# SparkFun_GPS_NEO_M9N_ANT_PROTO2.net
KiCad netlist of a schematic drawn in EAGLE
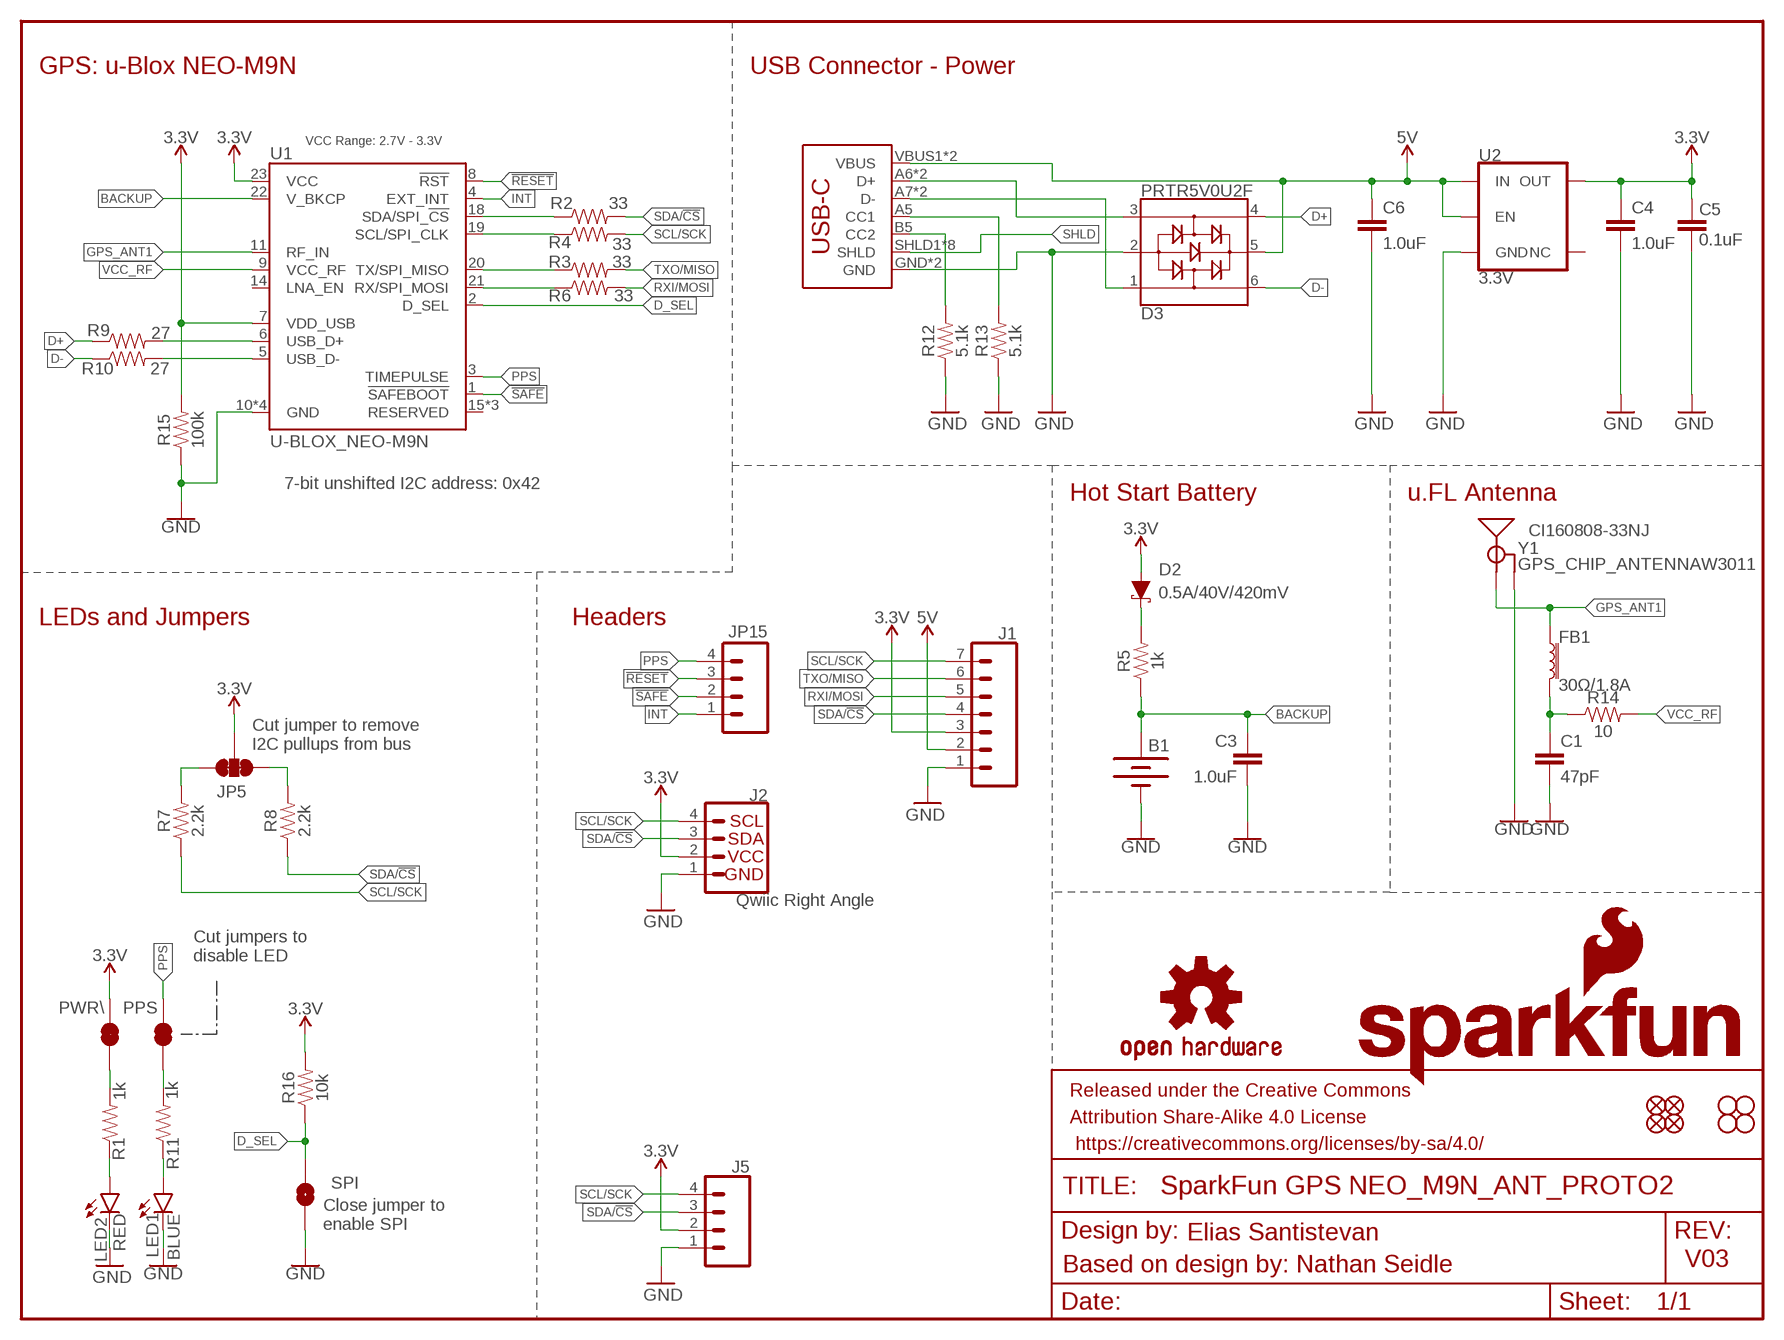
[diagram p0: schematic, sheet 1]

(export (version "E")
  (design (tool "Eeschema 10.0.6"))
  (components
    (comp (ref "B1")
      (value "6.8MM_COIN_CELL")
      (footprint "eagle-import:ML414H_IV01E")
      (libsource (lib "eagle-import") (part "ML414H_IV01E_BATTERY"))
    )
    (comp (ref "C1")
      (value "47pF")
      (footprint "eagle-import:0603")
      (libsource (lib "eagle-import") (part "47PF-0603-50V-5%"))
    )
    (comp (ref "C3")
      (value "1.0uF")
      (footprint "eagle-import:0603")
      (libsource (lib "eagle-import") (part "1.0UF-0603-16V-10%"))
    )
    (comp (ref "C4")
      (value "1.0uF")
      (footprint "eagle-import:0603")
      (libsource (lib "eagle-import") (part "1.0UF-0603-16V-10%"))
    )
    (comp (ref "C5")
      (value "0.1uF")
      (footprint "eagle-import:0603")
      (libsource (lib "eagle-import") (part "0.1UF-0603-25V-(+80/-20%)"))
    )
    (comp (ref "C6")
      (value "1.0uF")
      (footprint "eagle-import:0603")
      (libsource (lib "eagle-import") (part "1.0UF-0603-16V-10%"))
    )
    (comp (ref "D2")
      (value "0.5A/40V/420mV")
      (footprint "eagle-import:SOD-323")
      (libsource (lib "eagle-import") (part "DIODE-SCHOTTKY-PMEG4005EJ"))
    )
    (comp (ref "D3")
      (value "PRTR5V0U2F")
      (footprint "eagle-import:SOT886")
      (libsource (lib "eagle-import") (part "PRTR5V0U2F"))
    )
    (comp (ref "FB1")
      (value "30Ω/1.8A")
      (footprint "eagle-import:0603")
      (libsource (lib "eagle-import") (part "FERRITE_BEAD-0603"))
    )
    (comp (ref "FRAME1")
      (value "FRAME-LETTER")
      (footprint "eagle-import:CREATIVE_COMMONS")
      (libsource (lib "eagle-import") (part "FRAME-LETTER"))
    )
    (comp (ref "J1")
      (value "CONN_07NO_SILK")
      (footprint "eagle-import:1X07_NO_SILK")
      (libsource (lib "eagle-import") (part "CONN_07NO_SILK"))
    )
    (comp (ref "J2")
      (value "Qwiic Right Angle")
      (footprint "eagle-import:JST04_1MM_RA")
      (libsource (lib "eagle-import") (part "I2C_STANDARDQWIIC"))
    )
    (comp (ref "J3")
      (value "USB_C2-LAYER")
      (footprint "eagle-import:USB-C-16P")
      (libsource (lib "eagle-import") (part "USB_C2-LAYER"))
    )
    (comp (ref "J5")
      (value "CONN_041X04_NO_SILK")
      (footprint "eagle-import:1X04_NO_SILK")
      (libsource (lib "eagle-import") (part "CONN_041X04_NO_SILK"))
    )
    (comp (ref "JP5")
      (value "JUMPER-SMT_3_2-NC_TRACE_SILK")
      (footprint "eagle-import:SMT-JUMPER_3_2-NC_TRACE_SILK")
      (libsource (lib "eagle-import") (part "JUMPER-SMT_3_2-NC_TRACE_SILK"))
    )
    (comp (ref "JP15")
      (value "CONN_041X04_NO_SILK")
      (footprint "eagle-import:1X04_NO_SILK")
      (libsource (lib "eagle-import") (part "CONN_041X04_NO_SILK"))
    )
    (comp (ref "JP21")
      (value "FIDUCIALUFIDUCIAL")
      (footprint "eagle-import:MICRO-FIDUCIAL")
      (libsource (lib "eagle-import") (part "FIDUCIALUFIDUCIAL"))
    )
    (comp (ref "JP31")
      (value "STAND-OFF")
      (footprint "eagle-import:STAND-OFF")
      (libsource (lib "eagle-import") (part "STAND-OFF"))
    )
    (comp (ref "JP41")
      (value "STAND-OFF")
      (footprint "eagle-import:STAND-OFF")
      (libsource (lib "eagle-import") (part "STAND-OFF"))
    )
    (comp (ref "JP61")
      (value "FIDUCIALUFIDUCIAL")
      (footprint "eagle-import:MICRO-FIDUCIAL")
      (libsource (lib "eagle-import") (part "FIDUCIALUFIDUCIAL"))
    )
    (comp (ref "JP71")
      (value "FIDUCIALUFIDUCIAL")
      (footprint "eagle-import:MICRO-FIDUCIAL")
      (libsource (lib "eagle-import") (part "FIDUCIALUFIDUCIAL"))
    )
    (comp (ref "JP81")
      (value "FIDUCIALUFIDUCIAL")
      (footprint "eagle-import:MICRO-FIDUCIAL")
      (libsource (lib "eagle-import") (part "FIDUCIALUFIDUCIAL"))
    )
    (comp (ref "JP91")
      (value "STAND-OFF")
      (footprint "eagle-import:STAND-OFF")
      (libsource (lib "eagle-import") (part "STAND-OFF"))
    )
    (comp (ref "JP101")
      (value "STAND-OFF")
      (footprint "eagle-import:STAND-OFF")
      (libsource (lib "eagle-import") (part "STAND-OFF"))
    )
    (comp (ref "LED1")
      (value "BLUE")
      (footprint "eagle-import:LED-0603")
      (libsource (lib "eagle-import") (part "LED-BLUE0603"))
    )
    (comp (ref "LED2")
      (value "RED")
      (footprint "eagle-import:LED-0603")
      (libsource (lib "eagle-import") (part "LED-RED0603"))
    )
    (comp (ref "LOGO1")
      (value "OSHW-LOGOMINI")
      (footprint "eagle-import:OSHW-LOGO-MINI")
      (libsource (lib "eagle-import") (part "OSHW-LOGOMINI"))
    )
    (comp (ref "LOGO2")
      (value "SFE_LOGO_NAME_FLAME.1_INCH")
      (footprint "eagle-import:SFE_LOGO_NAME_FLAME_.1")
      (libsource (lib "eagle-import") (part "SFE_LOGO_NAME_FLAME.1_INCH"))
    )
    (comp (ref "PPS")
      (value "JUMPER-SMT_2_NC_TRACE_SILK")
      (footprint "eagle-import:SMT-JUMPER_2_NC_TRACE_SILK")
      (libsource (lib "eagle-import") (part "JUMPER-SMT_2_NC_TRACE_SILK"))
    )
    (comp (ref "PWR\\")
      (value "JUMPER-SMT_2_NC_TRACE_SILK")
      (footprint "eagle-import:SMT-JUMPER_2_NC_TRACE_SILK")
      (libsource (lib "eagle-import") (part "JUMPER-SMT_2_NC_TRACE_SILK"))
    )
    (comp (ref "R1")
      (value "1k")
      (footprint "eagle-import:0603")
      (libsource (lib "eagle-import") (part "1KOHM-0603-1/10W-1%"))
    )
    (comp (ref "R2")
      (value "33")
      (footprint "eagle-import:0603")
      (libsource (lib "eagle-import") (part "33OHM-0603-1/10W-1%"))
    )
    (comp (ref "R3")
      (value "33")
      (footprint "eagle-import:0603")
      (libsource (lib "eagle-import") (part "33OHM-0603-1/10W-1%"))
    )
    (comp (ref "R4")
      (value "33")
      (footprint "eagle-import:0603")
      (libsource (lib "eagle-import") (part "33OHM-0603-1/10W-1%"))
    )
    (comp (ref "R5")
      (value "1k")
      (footprint "eagle-import:0603")
      (libsource (lib "eagle-import") (part "1KOHM-0603-1/10W-1%"))
    )
    (comp (ref "R6")
      (value "33")
      (footprint "eagle-import:0603")
      (libsource (lib "eagle-import") (part "33OHM-0603-1/10W-1%"))
    )
    (comp (ref "R7")
      (value "2.2k")
      (footprint "eagle-import:0603")
      (libsource (lib "eagle-import") (part "2.2KOHM-0603-1/10W-1%"))
    )
    (comp (ref "R8")
      (value "2.2k")
      (footprint "eagle-import:0603")
      (libsource (lib "eagle-import") (part "2.2KOHM-0603-1/10W-1%"))
    )
    (comp (ref "R9")
      (value "27")
      (footprint "eagle-import:0603")
      (libsource (lib "eagle-import") (part "27OHM-0603-1/10W-1%"))
    )
    (comp (ref "R10")
      (value "27")
      (footprint "eagle-import:0603")
      (libsource (lib "eagle-import") (part "27OHM-0603-1/10W-1%"))
    )
    (comp (ref "R11")
      (value "1k")
      (footprint "eagle-import:0603")
      (libsource (lib "eagle-import") (part "1KOHM-0603-1/10W-1%"))
    )
    (comp (ref "R12")
      (value "5.1k")
      (footprint "eagle-import:0603")
      (libsource (lib "eagle-import") (part "5.1KOHM5.1KOHM-0603-1/10W-1%"))
    )
    (comp (ref "R13")
      (value "5.1k")
      (footprint "eagle-import:0603")
      (libsource (lib "eagle-import") (part "5.1KOHM5.1KOHM-0603-1/10W-1%"))
    )
    (comp (ref "R14")
      (value "10")
      (footprint "eagle-import:0603")
      (libsource (lib "eagle-import") (part "10OHM-0603-1/10W-1%"))
    )
    (comp (ref "R15")
      (value "100k")
      (footprint "eagle-import:0603")
      (libsource (lib "eagle-import") (part "100KOHM-0603-1/10W-1%"))
    )
    (comp (ref "R16")
      (value "10k")
      (footprint "eagle-import:0402")
      (libsource (lib "eagle-import") (part "10KOHM-0402-1/16W-1%"))
    )
    (comp (ref "SPI")
      (value "JUMPER-SMT_2_NO_SILK")
      (footprint "eagle-import:SMT-JUMPER_2_NO_SILK")
      (libsource (lib "eagle-import") (part "JUMPER-SMT_2_NO_SILK"))
    )
    (comp (ref "U1")
      (value "U-BLOX_NEO-M9N")
      (footprint "eagle-import:NEO-M9N")
      (libsource (lib "eagle-import") (part "U-BLOX_NEO-M9N"))
    )
    (comp (ref "U2")
      (value "3.3V")
      (footprint "eagle-import:SOT23-5")
      (libsource (lib "eagle-import") (part "V_REG_AP2112K-3.3V"))
    )
    (comp (ref "Y1")
      (value "GPS_CHIP_ANTENNAW3011")
      (footprint "eagle-import:W3011")
      (libsource (lib "eagle-import") (part "GPS_CHIP_ANTENNAW3011"))
    )
  )
  (nets
    (net (code "1") (name "/SDA{slash}~{CS}") (class "Default")
      (node (ref "J1") (pin "4") (pinfunction "4_4") (pintype "passive"))
      (node (ref "J2") (pin "3") (pinfunction "3_3") (pintype "passive"))
      (node (ref "J5") (pin "3") (pinfunction "3_3") (pintype "passive"))
      (node (ref "R2") (pin "2") (pinfunction "2_2") (pintype "passive"))
      (node (ref "R8") (pin "1") (pinfunction "1_1") (pintype "passive"))
    )
    (net (code "2") (name "/~{RESET}") (class "Default")
      (node (ref "JP15") (pin "3") (pinfunction "3_3") (pintype "passive"))
      (node (ref "U1") (pin "8") (pinfunction "~{RST}_8") (pintype "bidirectional"))
    )
    (net (code "3") (name "/~{SAFE}") (class "Default")
      (node (ref "JP15") (pin "2") (pinfunction "2_2") (pintype "passive"))
      (node (ref "U1") (pin "1") (pinfunction "~{SAFEBOOT}_1") (pintype "bidirectional"))
    )
    (net (code "4") (name "3.3V") (class "Default")
      (node (ref "C4") (pin "1") (pinfunction "1_1") (pintype "passive"))
      (node (ref "C5") (pin "2") (pinfunction "2_2") (pintype "passive"))
      (node (ref "D2") (pin "A") (pinfunction "A_A") (pintype "passive"))
      (node (ref "J1") (pin "3") (pinfunction "3_3") (pintype "passive"))
      (node (ref "J2") (pin "2") (pinfunction "2_2") (pintype "power_in"))
      (node (ref "J5") (pin "2") (pinfunction "2_2") (pintype "passive"))
      (node (ref "JP5") (pin "2") (pinfunction "2_2") (pintype "passive"))
      (node (ref "PWR\\") (pin "2") (pinfunction "2_2") (pintype "passive"))
      (node (ref "R15") (pin "2") (pinfunction "2_2") (pintype "passive"))
      (node (ref "R16") (pin "2") (pinfunction "2_2") (pintype "passive"))
      (node (ref "U1") (pin "23") (pinfunction "VCC_23") (pintype "bidirectional"))
      (node (ref "U1") (pin "7") (pinfunction "VDD_USB_7") (pintype "bidirectional"))
      (node (ref "U2") (pin "5") (pinfunction "OUT_5") (pintype "passive"))
    )
    (net (code "5") (name "5V") (class "Default")
      (node (ref "C6") (pin "1") (pinfunction "1_1") (pintype "passive"))
      (node (ref "D3") (pin "5") (pinfunction "5_5") (pintype "bidirectional"))
      (node (ref "J1") (pin "2") (pinfunction "2_2") (pintype "passive"))
      (node (ref "J3") (pin "VBUS1") (pinfunction "VBUS_VBUS1") (pintype "bidirectional"))
      (node (ref "J3") (pin "VBUS2") (pinfunction "VBUS_VBUS2") (pintype "bidirectional"))
      (node (ref "U2") (pin "1") (pinfunction "IN_1") (pintype "input"))
      (node (ref "U2") (pin "3") (pinfunction "EN_3") (pintype "input"))
    )
    (net (code "6") (name "BACKUP") (class "Default")
      (node (ref "B1") (pin "+") (pinfunction "+_+") (pintype "power_in"))
      (node (ref "C3") (pin "1") (pinfunction "1_1") (pintype "passive"))
      (node (ref "R5") (pin "1") (pinfunction "1_1") (pintype "passive"))
      (node (ref "U1") (pin "22") (pinfunction "V_BKCP_22") (pintype "bidirectional"))
    )
    (net (code "7") (name "D+") (class "Default")
      (node (ref "D3") (pin "4") (pinfunction "4_4") (pintype "bidirectional"))
      (node (ref "R9") (pin "1") (pinfunction "1_1") (pintype "passive"))
    )
    (net (code "8") (name "D-") (class "Default")
      (node (ref "D3") (pin "6") (pinfunction "6_6") (pintype "bidirectional"))
      (node (ref "R10") (pin "1") (pinfunction "1_1") (pintype "passive"))
    )
    (net (code "9") (name "D_SEL") (class "Default")
      (node (ref "R16") (pin "1") (pinfunction "1_1") (pintype "passive"))
      (node (ref "SPI") (pin "2") (pinfunction "2_2") (pintype "passive"))
      (node (ref "U1") (pin "2") (pinfunction "D_SEL_2") (pintype "bidirectional"))
    )
    (net (code "10") (name "GND") (class "Default")
      (node (ref "B1") (pin "-") (pinfunction "-_-") (pintype "power_in"))
      (node (ref "C1") (pin "2") (pinfunction "2_2") (pintype "passive"))
      (node (ref "C3") (pin "2") (pinfunction "2_2") (pintype "passive"))
      (node (ref "C4") (pin "2") (pinfunction "2_2") (pintype "passive"))
      (node (ref "C5") (pin "1") (pinfunction "1_1") (pintype "passive"))
      (node (ref "C6") (pin "2") (pinfunction "2_2") (pintype "passive"))
      (node (ref "D3") (pin "2") (pinfunction "2_2") (pintype "bidirectional"))
      (node (ref "J1") (pin "1") (pinfunction "1_1") (pintype "passive"))
      (node (ref "J2") (pin "1") (pinfunction "1_1") (pintype "power_in"))
      (node (ref "J3") (pin "GND") (pinfunction "GND_GND") (pintype "bidirectional"))
      (node (ref "J3") (pin "GND2") (pinfunction "GND_GND2") (pintype "bidirectional"))
      (node (ref "J5") (pin "1") (pinfunction "1_1") (pintype "passive"))
      (node (ref "LED1") (pin "C") (pinfunction "C_C") (pintype "passive"))
      (node (ref "LED2") (pin "C") (pinfunction "C_C") (pintype "passive"))
      (node (ref "R12") (pin "1") (pinfunction "1_1") (pintype "passive"))
      (node (ref "R13") (pin "1") (pinfunction "1_1") (pintype "passive"))
      (node (ref "R15") (pin "1") (pinfunction "1_1") (pintype "passive"))
      (node (ref "SPI") (pin "1") (pinfunction "1_1") (pintype "passive"))
      (node (ref "U1") (pin "10") (pinfunction "GND_10") (pintype "bidirectional"))
      (node (ref "U1") (pin "12") (pinfunction "GND_12") (pintype "bidirectional"))
      (node (ref "U1") (pin "13") (pinfunction "GND_13") (pintype "bidirectional"))
      (node (ref "U1") (pin "24") (pinfunction "GND_24") (pintype "bidirectional"))
      (node (ref "U2") (pin "2") (pinfunction "GND_2") (pintype "input"))
      (node (ref "Y1") (pin "2") (pinfunction "GND_2") (pintype "bidirectional"))
      (node (ref "Y1") (pin "3") (pinfunction "GND_3") (pintype "bidirectional"))
    )
    (net (code "11") (name "GPS_ANT1") (class "Default")
      (node (ref "FB1") (pin "1") (pinfunction "1_1") (pintype "passive"))
      (node (ref "U1") (pin "11") (pinfunction "RF_IN_11") (pintype "bidirectional"))
      (node (ref "Y1") (pin "1") (pinfunction "SIGNAL_1") (pintype "bidirectional"))
    )
    (net (code "12") (name "INT") (class "Default")
      (node (ref "JP15") (pin "1") (pinfunction "1_1") (pintype "passive"))
      (node (ref "U1") (pin "4") (pinfunction "EXT_INT_4") (pintype "bidirectional"))
    )
    (net (code "13") (name "Net-(C1-Pad1)") (class "Default")
      (node (ref "C1") (pin "1") (pinfunction "1_1") (pintype "passive"))
      (node (ref "FB1") (pin "2") (pinfunction "2_2") (pintype "passive"))
      (node (ref "R14") (pin "1") (pinfunction "1_1") (pintype "passive"))
    )
    (net (code "14") (name "Net-(D2-PadC)") (class "Default")
      (node (ref "D2") (pin "C") (pinfunction "C_C") (pintype "passive"))
      (node (ref "R5") (pin "2") (pinfunction "2_2") (pintype "passive"))
    )
    (net (code "15") (name "Net-(D3-Pad1)") (class "Default")
      (node (ref "D3") (pin "1") (pinfunction "1_1") (pintype "bidirectional"))
      (node (ref "J3") (pin "A7") (pinfunction "D-_A7") (pintype "bidirectional"))
      (node (ref "J3") (pin "B7") (pinfunction "D-_B7") (pintype "bidirectional"))
    )
    (net (code "16") (name "Net-(D3-Pad3)") (class "Default")
      (node (ref "D3") (pin "3") (pinfunction "3_3") (pintype "bidirectional"))
      (node (ref "J3") (pin "A6") (pinfunction "D+_A6") (pintype "bidirectional"))
      (node (ref "J3") (pin "B6") (pinfunction "D+_B6") (pintype "bidirectional"))
    )
    (net (code "17") (name "Net-(J3-CC1)") (class "Default")
      (node (ref "J3") (pin "A5") (pinfunction "CC1_A5") (pintype "bidirectional"))
      (node (ref "R13") (pin "2") (pinfunction "2_2") (pintype "passive"))
    )
    (net (code "18") (name "Net-(J3-CC2)") (class "Default")
      (node (ref "J3") (pin "B5") (pinfunction "CC2_B5") (pintype "bidirectional"))
      (node (ref "R12") (pin "2") (pinfunction "2_2") (pintype "passive"))
    )
    (net (code "19") (name "Net-(JP5-Pad1)") (class "Default")
      (node (ref "JP5") (pin "1") (pinfunction "1_1") (pintype "passive"))
      (node (ref "R8") (pin "2") (pinfunction "2_2") (pintype "passive"))
    )
    (net (code "20") (name "Net-(JP5-Pad3)") (class "Default")
      (node (ref "JP5") (pin "3") (pinfunction "3_3") (pintype "passive"))
      (node (ref "R7") (pin "2") (pinfunction "2_2") (pintype "passive"))
    )
    (net (code "21") (name "Net-(LED1-PadA)") (class "Default")
      (node (ref "LED1") (pin "A") (pinfunction "A_A") (pintype "passive"))
      (node (ref "R11") (pin "1") (pinfunction "1_1") (pintype "passive"))
    )
    (net (code "22") (name "Net-(LED2-PadA)") (class "Default")
      (node (ref "LED2") (pin "A") (pinfunction "A_A") (pintype "passive"))
      (node (ref "R1") (pin "1") (pinfunction "1_1") (pintype "passive"))
    )
    (net (code "23") (name "Net-(PPS-Pad1)") (class "Default")
      (node (ref "PPS") (pin "1") (pinfunction "1_1") (pintype "passive"))
      (node (ref "R11") (pin "2") (pinfunction "2_2") (pintype "passive"))
    )
    (net (code "24") (name "Net-(PWR\\-Pad1)") (class "Default")
      (node (ref "PWR\\") (pin "1") (pinfunction "1_1") (pintype "passive"))
      (node (ref "R1") (pin "2") (pinfunction "2_2") (pintype "passive"))
    )
    (net (code "25") (name "Net-(U1-RX{slash}SPI_MOSI)") (class "Default")
      (node (ref "R6") (pin "1") (pinfunction "1_1") (pintype "passive"))
      (node (ref "U1") (pin "21") (pinfunction "RX/SPI_MOSI_21") (pintype "bidirectional"))
    )
    (net (code "26") (name "Net-(U1-SCL{slash}SPI_CLK)") (class "Default")
      (node (ref "R4") (pin "1") (pinfunction "1_1") (pintype "passive"))
      (node (ref "U1") (pin "19") (pinfunction "SCL/SPI_CLK_19") (pintype "bidirectional"))
    )
    (net (code "27") (name "Net-(U1-SDA{slash}SPI_~{CS})") (class "Default")
      (node (ref "R2") (pin "1") (pinfunction "1_1") (pintype "passive"))
      (node (ref "U1") (pin "18") (pinfunction "SDA/SPI_~{CS}_18") (pintype "bidirectional"))
    )
    (net (code "28") (name "Net-(U1-TX{slash}SPI_MISO)") (class "Default")
      (node (ref "R3") (pin "1") (pinfunction "1_1") (pintype "passive"))
      (node (ref "U1") (pin "20") (pinfunction "TX/SPI_MISO_20") (pintype "bidirectional"))
    )
    (net (code "29") (name "Net-(U1-USB_D+)") (class "Default")
      (node (ref "R9") (pin "2") (pinfunction "2_2") (pintype "passive"))
      (node (ref "U1") (pin "6") (pinfunction "USB_D+_6") (pintype "bidirectional"))
    )
    (net (code "30") (name "Net-(U1-USB_D-)") (class "Default")
      (node (ref "R10") (pin "2") (pinfunction "2_2") (pintype "passive"))
      (node (ref "U1") (pin "5") (pinfunction "USB_D-_5") (pintype "bidirectional"))
    )
    (net (code "31") (name "PPS") (class "Default")
      (node (ref "JP15") (pin "4") (pinfunction "4_4") (pintype "passive"))
      (node (ref "PPS") (pin "2") (pinfunction "2_2") (pintype "passive"))
      (node (ref "U1") (pin "3") (pinfunction "TIMEPULSE_3") (pintype "bidirectional"))
    )
    (net (code "32") (name "RXI{slash}MOSI") (class "Default")
      (node (ref "J1") (pin "5") (pinfunction "5_5") (pintype "passive"))
      (node (ref "R6") (pin "2") (pinfunction "2_2") (pintype "passive"))
    )
    (net (code "33") (name "SCL{slash}SCK") (class "Default")
      (node (ref "J1") (pin "7") (pinfunction "7_7") (pintype "passive"))
      (node (ref "J2") (pin "4") (pinfunction "4_4") (pintype "passive"))
      (node (ref "J5") (pin "4") (pinfunction "4_4") (pintype "passive"))
      (node (ref "R4") (pin "2") (pinfunction "2_2") (pintype "passive"))
      (node (ref "R7") (pin "1") (pinfunction "1_1") (pintype "passive"))
    )
    (net (code "34") (name "SHLD") (class "Default")
      (node (ref "J3") (pin "SHLD1") (pinfunction "SHLD_SHLD1") (pintype "bidirectional"))
      (node (ref "J3") (pin "SHLD2") (pinfunction "SHLD_SHLD2") (pintype "bidirectional"))
      (node (ref "J3") (pin "SHLD3") (pinfunction "SHLD_SHLD3") (pintype "bidirectional"))
      (node (ref "J3") (pin "SHLD4") (pinfunction "SHLD_SHLD4") (pintype "bidirectional"))
      (node (ref "J3") (pin "SHLD5") (pinfunction "SHLD_SHLD5") (pintype "bidirectional"))
      (node (ref "J3") (pin "SHLD6") (pinfunction "SHLD_SHLD6") (pintype "bidirectional"))
      (node (ref "J3") (pin "SHLD7") (pinfunction "SHLD_SHLD7") (pintype "bidirectional"))
      (node (ref "J3") (pin "SHLD8") (pinfunction "SHLD_SHLD8") (pintype "bidirectional"))
    )
    (net (code "35") (name "TXO{slash}MISO") (class "Default")
      (node (ref "J1") (pin "6") (pinfunction "6_6") (pintype "passive"))
      (node (ref "R3") (pin "2") (pinfunction "2_2") (pintype "passive"))
    )
    (net (code "36") (name "VCC_RF") (class "Default")
      (node (ref "R14") (pin "2") (pinfunction "2_2") (pintype "passive"))
      (node (ref "U1") (pin "9") (pinfunction "VCC_RF_9") (pintype "bidirectional"))
    )
    (net (code "37") (name "unconnected-(U1-LNA_EN-Pad14)") (class "Default")
      (node (ref "U1") (pin "14") (pinfunction "LNA_EN_14") (pintype "bidirectional"))
    )
    (net (code "38") (name "unconnected-(U1-RESERVED-Pad15)") (class "Default")
      (node (ref "U1") (pin "15") (pinfunction "RESERVED_15") (pintype "no_connect"))
    )
    (net (code "39") (name "unconnected-(U1-RESERVED-Pad16)") (class "Default")
      (node (ref "U1") (pin "16") (pinfunction "RESERVED_16") (pintype "no_connect"))
    )
    (net (code "40") (name "unconnected-(U1-RESERVED-Pad17)") (class "Default")
      (node (ref "U1") (pin "17") (pinfunction "RESERVED_17") (pintype "no_connect"))
    )
    (net (code "41") (name "unconnected-(U2-NC-Pad4)") (class "Default")
      (node (ref "U2") (pin "4") (pinfunction "NC_4") (pintype "no_connect"))
    )
  )
)
